# bt.net
KiCad netlist of a schematic drawn in Altium Designer
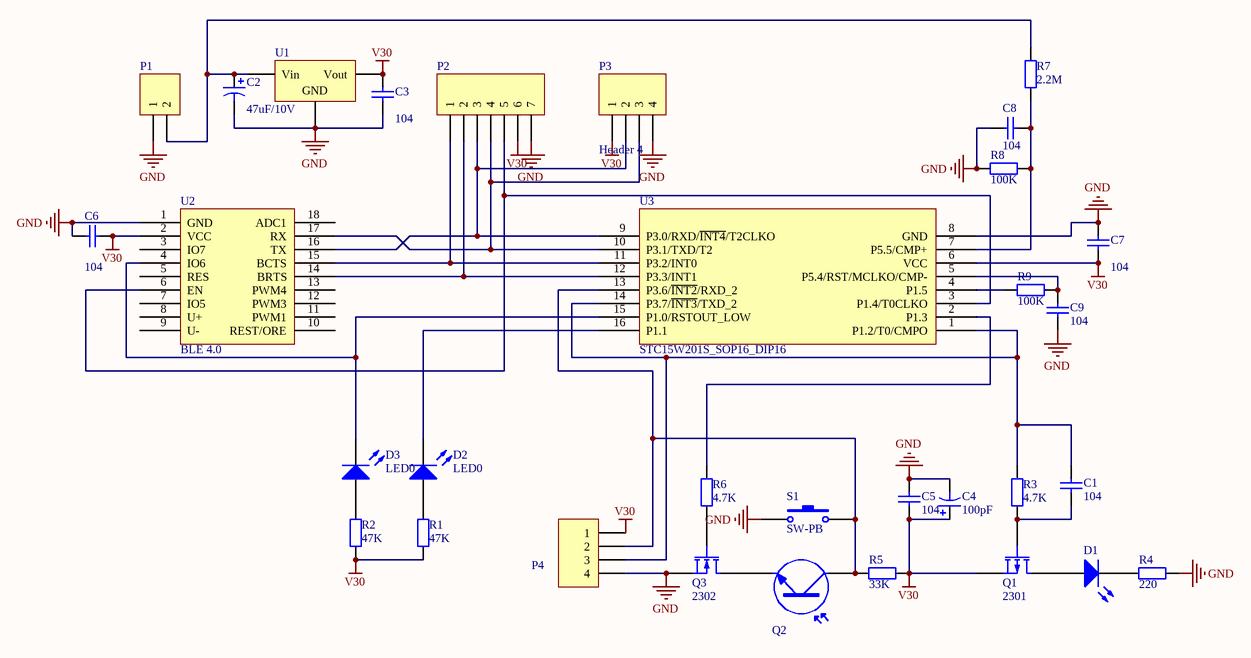
[diagram p0: bt.SchDoc]

(export (version "E")
  (design (tool "Eeschema 10.0.6"))
  (components
    (comp (ref "C1")
      (value "Cap Semi")
      (footprint "C0805")
      (description "Capacitor (Semiconductor SIM Model)")
      (fields (field (name "47UF/10V") "104") (field (name "PUBLISHER") "Altium Limited"))
      (libsource (lib "Miscellaneous Devices") (part "Cap Semi"))
    )
    (comp (ref "C2")
      (value "47uF/10V")
      (footprint "3528")
      (description "Polarized Capacitor (Radial)")
      (fields (field (name "Comment") "Cap Pol1") (field (name "PUBLISHER") "Altium Limited"))
      (libsource (lib "Miscellaneous Devices") (part "Cap Pol1"))
    )
    (comp (ref "C3")
      (value "Cap Semi")
      (footprint "C0805")
      (description "Capacitor (Semiconductor SIM Model)")
      (fields (field (name "47UF/10V") "104") (field (name "PUBLISHER") "Altium Limited"))
      (libsource (lib "Miscellaneous Devices") (part "Cap Semi"))
    )
    (comp (ref "C4")
      (value "100pF")
      (footprint "3528")
      (description "Polarized Capacitor (Radial)")
      (fields (field (name "Comment") "Cap Pol1") (field (name "PUBLISHER") "Altium Limited"))
      (libsource (lib "Miscellaneous Devices") (part "Cap Pol1"))
    )
    (comp (ref "C5")
      (value "Cap Semi")
      (footprint "C0805")
      (description "Capacitor (Semiconductor SIM Model)")
      (fields (field (name "47UF/10V") "104") (field (name "PUBLISHER") "Altium Limited"))
      (libsource (lib "Miscellaneous Devices") (part "Cap Semi"))
    )
    (comp (ref "C6")
      (value "Cap Semi")
      (footprint "C0805")
      (description "Capacitor (Semiconductor SIM Model)")
      (fields (field (name "47UF/10V") "104") (field (name "PUBLISHER") "Altium Limited"))
      (libsource (lib "Miscellaneous Devices") (part "Cap Semi"))
    )
    (comp (ref "C7")
      (value "Cap Semi")
      (footprint "C0805")
      (description "Capacitor (Semiconductor SIM Model)")
      (fields (field (name "47UF/10V") "104") (field (name "PUBLISHER") "Altium Limited"))
      (libsource (lib "Miscellaneous Devices") (part "Cap Semi"))
    )
    (comp (ref "C8")
      (value "Cap Semi")
      (footprint "C0805")
      (description "Capacitor (Semiconductor SIM Model)")
      (fields (field (name "47UF/10V") "104") (field (name "PUBLISHER") "Altium Limited"))
      (libsource (lib "Miscellaneous Devices") (part "Cap Semi"))
    )
    (comp (ref "C9")
      (value "Cap Semi")
      (footprint "C0805")
      (description "Capacitor (Semiconductor SIM Model)")
      (fields (field (name "47UF/10V") "104") (field (name "PUBLISHER") "Altium Limited"))
      (libsource (lib "Miscellaneous Devices") (part "Cap Semi"))
    )
    (comp (ref "D1")
      (value "LED0")
      (footprint "LED1")
      (description "Typical INFRARED GaAs LED")
      (fields (field (name "PUBLISHER") "Altium Limited"))
      (libsource (lib "Miscellaneous Devices") (part "LED0"))
    )
    (comp (ref "D2")
      (value "LED0")
      (footprint "0805")
      (description "Typical INFRARED GaAs LED")
      (fields (field (name "PUBLISHER") "Altium Limited"))
      (libsource (lib "Miscellaneous Devices") (part "LED0"))
    )
    (comp (ref "D3")
      (value "LED0")
      (footprint "0805")
      (description "Typical INFRARED GaAs LED")
      (fields (field (name "PUBLISHER") "Altium Limited"))
      (libsource (lib "Miscellaneous Devices") (part "LED0"))
    )
    (comp (ref "P1")
      (value "Header 2")
      (footprint "HDR1X2")
      (description "Header, 2-Pin")
      (fields (field (name "PUBLISHER") "Altium Limited"))
      (libsource (lib "Miscellaneous Connectors") (part "Header 2"))
    )
    (comp (ref "P2")
      (value "Header 7")
      (footprint "HDR1X7")
      (description "Header, 7-Pin")
      (fields (field (name "PUBLISHER") "Altium Limited"))
      (libsource (lib "Miscellaneous Connectors") (part "Header 7"))
    )
    (comp (ref "P3")
      (value "Header 4")
      (footprint "HDR1X4")
      (description "Header, 4-Pin")
      (fields (field (name "PUBLISHER") "Altium Limited"))
      (libsource (lib "") (part "Header 4_1"))
    )
    (comp (ref "P4")
      (value "Header 4")
      (footprint "HDR1X4")
      (description "Header, 4-Pin")
      (fields (field (name "PUBLISHER") "Altium Limited"))
      (libsource (lib "Miscellaneous Connectors") (part "Header 4"))
    )
    (comp (ref "Q1")
      (value "2301")
      (footprint "SOT-23 - LDO")
      (description "P-Channel MOSFET")
      (fields (field (name "PUBLISHER") "Altium Limited"))
      (libsource (lib "Miscellaneous Devices") (part "MOSFET-P"))
    )
    (comp (ref "Q2")
      (value "Photo NPN")
      (footprint "SIP3")
      (description "NPN Phototransistor")
      (fields (field (name "PUBLISHER") "Altium Limited"))
      (libsource (lib "Miscellaneous Devices") (part "Photo NPN"))
    )
    (comp (ref "Q3")
      (value "2302")
      (footprint "SOT-23 - LDO")
      (description "N-Channel MOSFET")
      (fields (field (name "PUBLISHER") "Altium Limited"))
      (libsource (lib "Miscellaneous Devices") (part "MOSFET-N"))
    )
    (comp (ref "R1")
      (value "47K")
      (footprint "C0805")
      (description "Resistor")
      (fields (field (name "Comment") "Res2") (field (name "PUBLISHER") "Altium Limited"))
      (libsource (lib "Miscellaneous Devices") (part "Res2"))
    )
    (comp (ref "R2")
      (value "47K")
      (footprint "C0805")
      (description "Resistor")
      (fields (field (name "Comment") "Res2") (field (name "PUBLISHER") "Altium Limited"))
      (libsource (lib "Miscellaneous Devices") (part "Res2"))
    )
    (comp (ref "R3")
      (value "4.7K")
      (footprint "C0805")
      (description "Resistor")
      (fields (field (name "Comment") "Res2") (field (name "PUBLISHER") "Altium Limited"))
      (libsource (lib "Miscellaneous Devices") (part "Res2"))
    )
    (comp (ref "R4")
      (value "220")
      (footprint "C0805")
      (description "Resistor")
      (fields (field (name "Comment") "Res2") (field (name "PUBLISHER") "Altium Limited"))
      (libsource (lib "") (part "Res2_1"))
    )
    (comp (ref "R5")
      (value "33K")
      (footprint "C0805")
      (description "Resistor")
      (fields (field (name "Comment") "Res2") (field (name "PUBLISHER") "Altium Limited"))
      (libsource (lib "") (part "Res2_1"))
    )
    (comp (ref "R6")
      (value "4.7K")
      (footprint "C0805")
      (description "Resistor")
      (fields (field (name "Comment") "Res2") (field (name "PUBLISHER") "Altium Limited"))
      (libsource (lib "Miscellaneous Devices") (part "Res2"))
    )
    (comp (ref "R7")
      (value "2.2M")
      (footprint "C0805")
      (description "Resistor")
      (fields (field (name "Comment") "Res2") (field (name "PUBLISHER") "Altium Limited"))
      (libsource (lib "Miscellaneous Devices") (part "Res2"))
    )
    (comp (ref "R8")
      (value "100K")
      (footprint "C0805")
      (description "Resistor")
      (fields (field (name "Comment") "Res2") (field (name "PUBLISHER") "Altium Limited"))
      (libsource (lib "") (part "Res2_1"))
    )
    (comp (ref "R9")
      (value "100K")
      (footprint "C0805")
      (description "Resistor")
      (fields (field (name "Comment") "Res2") (field (name "PUBLISHER") "Altium Limited"))
      (libsource (lib "") (part "Res2_1"))
    )
    (comp (ref "S1")
      (value "SW-PB")
      (footprint "KEY4")
      (description "Switch")
      (fields (field (name "PUBLISHER") "Altium Limited"))
      (libsource (lib "Miscellaneous Devices") (part "SW-PB"))
    )
    (comp (ref "U1")
      (value "XC6206P302PR")
      (footprint "SOT-23 - LDO")
      (description "Voltage Regulator")
      (fields (field (name "PUBLISHER") "Altium Limited"))
      (libsource (lib "Miscellaneous Devices") (part "Volt Reg"))
    )
    (comp (ref "U2") (value "BLE 4.0") (footprint "BLE4.0") (libsource (lib "AD封装库") (part "BLE 4.0")))
    (comp (ref "U3")
      (value "STC15W201S_SOP16_DIP16")
      (footprint "SOP16")
      (libsource (lib "stcmcu_altium_lib") (part "STC15W201S_SOP16_DIP16"))
    )
  )
  (nets
    (net (code "1") (name "GND") (class "Default")
      (node (ref "C2") (pin "2") (pinfunction "2_2") (pintype "passive"))
      (node (ref "C3") (pin "1") (pinfunction "1_1") (pintype "passive"))
      (node (ref "C4") (pin "2") (pinfunction "2_2") (pintype "passive"))
      (node (ref "C5") (pin "1") (pinfunction "1_1") (pintype "passive"))
      (node (ref "C6") (pin "1") (pinfunction "1_1") (pintype "passive"))
      (node (ref "C7") (pin "2") (pinfunction "2_2") (pintype "passive"))
      (node (ref "C8") (pin "1") (pinfunction "1_1") (pintype "passive"))
      (node (ref "C9") (pin "2") (pinfunction "2_2") (pintype "passive"))
      (node (ref "P1") (pin "1") (pinfunction "1_1") (pintype "passive"))
      (node (ref "P2") (pin "7") (pinfunction "7_7") (pintype "passive"))
      (node (ref "P3") (pin "4") (pinfunction "4_4") (pintype "passive"))
      (node (ref "P4") (pin "4") (pinfunction "4_4") (pintype "passive"))
      (node (ref "Q3") (pin "2") (pinfunction "S_2") (pintype "passive"))
      (node (ref "R4") (pin "1") (pinfunction "1_1") (pintype "passive"))
      (node (ref "R8") (pin "2") (pinfunction "2_2") (pintype "passive"))
      (node (ref "S1") (pin "1") (pinfunction "1_1") (pintype "passive"))
      (node (ref "U1") (pin "1") (pinfunction "GND_1") (pintype "passive"))
      (node (ref "U2") (pin "1") (pinfunction "GND_1") (pintype "passive"))
      (node (ref "U3") (pin "8") (pinfunction "GND_8") (pintype "passive"))
    )
    (net (code "2") (name "Net-(D1-A)") (class "Default")
      (node (ref "D1") (pin "1") (pinfunction "A_1") (pintype "passive"))
      (node (ref "Q1") (pin "2") (pinfunction "D_2") (pintype "passive"))
    )
    (net (code "3") (name "Net-(D1-K)") (class "Default")
      (node (ref "D1") (pin "2") (pinfunction "K_2") (pintype "passive"))
      (node (ref "R4") (pin "2") (pinfunction "2_2") (pintype "passive"))
    )
    (net (code "4") (name "Net-(D2-A)") (class "Default")
      (node (ref "D2") (pin "1") (pinfunction "A_1") (pintype "passive"))
      (node (ref "R1") (pin "2") (pinfunction "2_2") (pintype "passive"))
    )
    (net (code "5") (name "Net-(D2-K)") (class "Default")
      (node (ref "D2") (pin "2") (pinfunction "K_2") (pintype "passive"))
      (node (ref "U3") (pin "16") (pinfunction "P1.1_16") (pintype "passive"))
    )
    (net (code "6") (name "Net-(D3-A)") (class "Default")
      (node (ref "D3") (pin "1") (pinfunction "A_1") (pintype "passive"))
      (node (ref "R2") (pin "2") (pinfunction "2_2") (pintype "passive"))
    )
    (net (code "7") (name "Net-(D3-K)") (class "Default")
      (node (ref "D3") (pin "2") (pinfunction "K_2") (pintype "passive"))
      (node (ref "U2") (pin "4") (pinfunction "IO6_4") (pintype "passive"))
      (node (ref "U3") (pin "15") (pinfunction "P1.0/RSTOUT_LOW_15") (pintype "passive"))
    )
    (net (code "8") (name "Net-(Q1-G)") (class "Default")
      (node (ref "C1") (pin "2") (pinfunction "2_2") (pintype "passive"))
      (node (ref "Q1") (pin "1") (pinfunction "G_1") (pintype "passive"))
      (node (ref "R3") (pin "1") (pinfunction "1_1") (pintype "passive"))
    )
    (net (code "9") (name "Net-(Q2-C)") (class "Default")
      (node (ref "P4") (pin "2") (pinfunction "2_2") (pintype "passive"))
      (node (ref "Q2") (pin "1") (pinfunction "C_1") (pintype "passive"))
      (node (ref "R5") (pin "2") (pinfunction "2_2") (pintype "passive"))
      (node (ref "S1") (pin "3") (pinfunction "3_3") (pintype "passive"))
      (node (ref "U3") (pin "13") (pinfunction "P3.6/~{INT2}/RXD_2_13") (pintype "passive"))
    )
    (net (code "10") (name "Net-(Q2-E)") (class "Default")
      (node (ref "Q2") (pin "2") (pinfunction "E_2") (pintype "passive"))
      (node (ref "Q3") (pin "3") (pinfunction "D_3") (pintype "passive"))
    )
    (net (code "11") (name "Net-(Q3-G)") (class "Default")
      (node (ref "Q3") (pin "1") (pinfunction "G_1") (pintype "passive"))
      (node (ref "R6") (pin "1") (pinfunction "1_1") (pintype "passive"))
    )
    (net (code "12") (name "Net-(U1-Vin)") (class "Default")
      (node (ref "C2") (pin "1") (pinfunction "1_1") (pintype "passive"))
      (node (ref "P1") (pin "2") (pinfunction "2_2") (pintype "passive"))
      (node (ref "R7") (pin "2") (pinfunction "2_2") (pintype "passive"))
      (node (ref "U1") (pin "3") (pinfunction "Vin_3") (pintype "passive"))
    )
    (net (code "13") (name "Net-(U2-BCTS)") (class "Default")
      (node (ref "P2") (pin "1") (pinfunction "1_1") (pintype "passive"))
      (node (ref "U2") (pin "15") (pinfunction "BCTS_15") (pintype "passive"))
      (node (ref "U3") (pin "11") (pinfunction "P3.2/INT0_11") (pintype "passive"))
    )
    (net (code "14") (name "Net-(U2-BRTS)") (class "Default")
      (node (ref "P2") (pin "2") (pinfunction "2_2") (pintype "passive"))
      (node (ref "U2") (pin "14") (pinfunction "BRTS_14") (pintype "passive"))
      (node (ref "U3") (pin "12") (pinfunction "P3.3/INT1_12") (pintype "passive"))
    )
    (net (code "15") (name "Net-(U2-EN)") (class "Default")
      (node (ref "P2") (pin "5") (pinfunction "5_5") (pintype "passive"))
      (node (ref "U2") (pin "6") (pinfunction "EN_6") (pintype "passive"))
      (node (ref "U3") (pin "3") (pinfunction "P1.4/T0CLKO_3") (pintype "passive"))
    )
    (net (code "16") (name "Net-(U2-RX)") (class "Default")
      (node (ref "P2") (pin "4") (pinfunction "4_4") (pintype "passive"))
      (node (ref "P3") (pin "3") (pinfunction "3_3") (pintype "passive"))
      (node (ref "U2") (pin "17") (pinfunction "RX_17") (pintype "passive"))
      (node (ref "U3") (pin "10") (pinfunction "P3.1/TXD/T2_10") (pintype "passive"))
    )
    (net (code "17") (name "Net-(U2-TX)") (class "Default")
      (node (ref "P2") (pin "3") (pinfunction "3_3") (pintype "passive"))
      (node (ref "P3") (pin "2") (pinfunction "2_2") (pintype "passive"))
      (node (ref "U2") (pin "16") (pinfunction "TX_16") (pintype "passive"))
      (node (ref "U3") (pin "9") (pinfunction "P3.0/RXD/~{INT4}/T2CLKO_9") (pintype "passive"))
    )
    (net (code "18") (name "Net-(U3-P1.2{slash}T0{slash}CMPO)") (class "Default")
      (node (ref "C1") (pin "1") (pinfunction "1_1") (pintype "passive"))
      (node (ref "P4") (pin "3") (pinfunction "3_3") (pintype "passive"))
      (node (ref "R3") (pin "2") (pinfunction "2_2") (pintype "passive"))
      (node (ref "U3") (pin "1") (pinfunction "P1.2/T0/CMPO_1") (pintype "passive"))
      (node (ref "U3") (pin "14") (pinfunction "P3.7/~{INT3}/TXD_2_14") (pintype "passive"))
    )
    (net (code "19") (name "Net-(U3-P1.3)") (class "Default")
      (node (ref "R6") (pin "2") (pinfunction "2_2") (pintype "passive"))
      (node (ref "U3") (pin "2") (pinfunction "P1.3_2") (pintype "passive"))
    )
    (net (code "20") (name "Net-(U3-P1.5)") (class "Default")
      (node (ref "R9") (pin "2") (pinfunction "2_2") (pintype "passive"))
      (node (ref "U3") (pin "4") (pinfunction "P1.5_4") (pintype "passive"))
    )
    (net (code "21") (name "Net-(U3-P5.4{slash}RST{slash}MCLKO{slash}CMP-)") (class "Default")
      (node (ref "C9") (pin "1") (pinfunction "1_1") (pintype "passive"))
      (node (ref "R9") (pin "1") (pinfunction "1_1") (pintype "passive"))
      (node (ref "U3") (pin "5") (pinfunction "P5.4/RST/MCLKO/CMP-_5") (pintype "passive"))
    )
    (net (code "22") (name "Net-(U3-P5.5{slash}CMP+)") (class "Default")
      (node (ref "C8") (pin "2") (pinfunction "2_2") (pintype "passive"))
      (node (ref "R7") (pin "1") (pinfunction "1_1") (pintype "passive"))
      (node (ref "R8") (pin "1") (pinfunction "1_1") (pintype "passive"))
      (node (ref "U3") (pin "7") (pinfunction "P5.5/CMP+_7") (pintype "passive"))
    )
    (net (code "23") (name "V30") (class "Default")
      (node (ref "C3") (pin "2") (pinfunction "2_2") (pintype "passive"))
      (node (ref "C4") (pin "1") (pinfunction "1_1") (pintype "passive"))
      (node (ref "C5") (pin "2") (pinfunction "2_2") (pintype "passive"))
      (node (ref "C6") (pin "2") (pinfunction "2_2") (pintype "passive"))
      (node (ref "C7") (pin "1") (pinfunction "1_1") (pintype "passive"))
      (node (ref "P2") (pin "6") (pinfunction "6_6") (pintype "passive"))
      (node (ref "P3") (pin "1") (pinfunction "1_1") (pintype "passive"))
      (node (ref "P4") (pin "1") (pinfunction "1_1") (pintype "passive"))
      (node (ref "Q1") (pin "3") (pinfunction "S_3") (pintype "passive"))
      (node (ref "R1") (pin "1") (pinfunction "1_1") (pintype "passive"))
      (node (ref "R2") (pin "1") (pinfunction "1_1") (pintype "passive"))
      (node (ref "R5") (pin "1") (pinfunction "1_1") (pintype "passive"))
      (node (ref "U1") (pin "2") (pinfunction "Vout_2") (pintype "passive"))
      (node (ref "U2") (pin "2") (pinfunction "VCC_2") (pintype "passive"))
      (node (ref "U3") (pin "6") (pinfunction "VCC_6") (pintype "passive"))
    )
    (net (code "24") (name "unconnected-(U2-ADC1-Pad18)") (class "Default")
      (node (ref "U2") (pin "18") (pinfunction "ADC1_18") (pintype "passive"))
    )
    (net (code "25") (name "unconnected-(U2-IO5-Pad7)") (class "Default")
      (node (ref "U2") (pin "7") (pinfunction "IO5_7") (pintype "passive"))
    )
    (net (code "26") (name "unconnected-(U2-IO7-Pad3)") (class "Default")
      (node (ref "U2") (pin "3") (pinfunction "IO7_3") (pintype "passive"))
    )
    (net (code "27") (name "unconnected-(U2-PWM1-Pad11)") (class "Default")
      (node (ref "U2") (pin "11") (pinfunction "PWM1_11") (pintype "passive"))
    )
    (net (code "28") (name "unconnected-(U2-PWM3-Pad12)") (class "Default")
      (node (ref "U2") (pin "12") (pinfunction "PWM3_12") (pintype "passive"))
    )
    (net (code "29") (name "unconnected-(U2-PWM4-Pad13)") (class "Default")
      (node (ref "U2") (pin "13") (pinfunction "PWM4_13") (pintype "passive"))
    )
    (net (code "30") (name "unconnected-(U2-RES-Pad5)") (class "Default")
      (node (ref "U2") (pin "5") (pinfunction "RES_5") (pintype "passive"))
    )
    (net (code "31") (name "unconnected-(U2-REST{slash}ORE-Pad10)") (class "Default")
      (node (ref "U2") (pin "10") (pinfunction "REST/ORE_10") (pintype "passive"))
    )
    (net (code "32") (name "unconnected-(U2-U+-Pad8)") (class "Default")
      (node (ref "U2") (pin "8") (pinfunction "U+_8") (pintype "passive"))
    )
    (net (code "33") (name "unconnected-(U2-U--Pad9)") (class "Default")
      (node (ref "U2") (pin "9") (pinfunction "U-_9") (pintype "passive"))
    )
  )
)
